# USB.net
KiCad netlist of a schematic drawn in Altium Designer
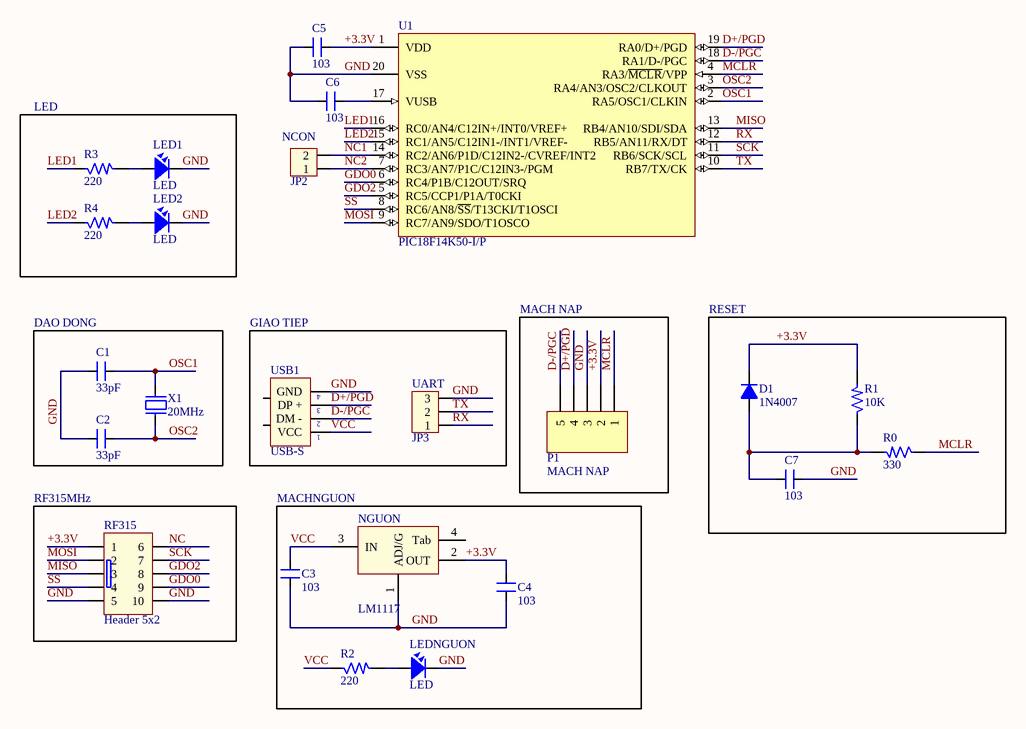
[diagram p0: USB.SchDoc]

(export (version "E")
  (design (tool "Eeschema 10.0.6"))
  (components
    (comp (ref "C1")
      (value "33pF")
      (footprint "SM-0805")
      (description "Cap SMD")
      (libsource (lib "syhaunguyen") (part "CM"))
    )
    (comp (ref "C2")
      (value "33pF")
      (footprint "SM-0805")
      (description "Cap SMD")
      (libsource (lib "syhaunguyen") (part "CM"))
    )
    (comp (ref "C3")
      (value "103")
      (footprint "SM-0805")
      (description "Cap SMD")
      (libsource (lib "syhaunguyen") (part "CM"))
    )
    (comp (ref "C4")
      (value "103")
      (footprint "SM-0805")
      (description "Cap SMD")
      (libsource (lib "syhaunguyen") (part "CM"))
    )
    (comp (ref "C5")
      (value "103")
      (footprint "SM-0805")
      (description "Cap SMD")
      (libsource (lib "syhaunguyen") (part "CM"))
    )
    (comp (ref "C6")
      (value "103")
      (footprint "CP1/2.5_SM")
      (description "Cap SMD")
      (libsource (lib "syhaunguyen") (part "CM"))
    )
    (comp (ref "C7")
      (value "103")
      (footprint "SM-0805")
      (description "Cap SMD")
      (libsource (lib "syhaunguyen") (part "CM"))
    )
    (comp (ref "D1")
      (value "1N4007")
      (footprint "D1A")
      (description "Diode 1A")
      (libsource (lib "syhaunguyen") (part "D1A"))
    )
    (comp (ref "LED1")
      (value "LED")
      (footprint "LED-3")
      (description "LED Single colour Green and Red")
      (libsource (lib "syhaunguyen") (part "LED"))
    )
    (comp (ref "LED2")
      (value "LED")
      (footprint "LED-3")
      (description "LED Single colour Green and Red")
      (libsource (lib "syhaunguyen") (part "LED"))
    )
    (comp (ref "LEDNGUON")
      (value "LED")
      (footprint "LED-3")
      (description "LED Single colour Green and Red")
      (libsource (lib "syhaunguyen") (part "LED"))
    )
    (comp (ref "NCON")
      (value "JP2")
      (footprint "CON2")
      (description "Connector 2")
      (libsource (lib "syhaunguyen") (part "Con2"))
    )
    (comp (ref "NGUON")
      (value "LM1117")
      (footprint "SOT223-4N")
      (description "3v3")
      (libsource (lib "syhaunguyen") (part "LM1117"))
    )
    (comp (ref "P1")
      (value "MACH NAP")
      (footprint "CON5")
      (description "Header, 5-Pin, Right Angle")
      (fields (field (name "PUBLISHER") "Altium Limited"))
      (libsource (lib "Miscellaneous Connectors") (part "Header 5H"))
    )
    (comp (ref "R0")
      (value "330")
      (footprint "SM-0805")
      (description "Resistor 1/4W")
      (libsource (lib "syhaunguyen") (part "R"))
    )
    (comp (ref "R1")
      (value "10K")
      (footprint "SM-0805")
      (description "Resistor 1/4W")
      (libsource (lib "syhaunguyen") (part "R"))
    )
    (comp (ref "R2")
      (value "220")
      (footprint "SM-0805")
      (description "Resistor 1/4W")
      (libsource (lib "syhaunguyen") (part "R"))
    )
    (comp (ref "R3")
      (value "220")
      (footprint "SM-0805")
      (description "Resistor 1/4W")
      (libsource (lib "syhaunguyen") (part "R"))
    )
    (comp (ref "R4")
      (value "220")
      (footprint "SM-0805")
      (description "Resistor 1/4W")
      (libsource (lib "syhaunguyen") (part "R"))
    )
    (comp (ref "RF315")
      (value "Header 5x2")
      (footprint "HED2X5_cen")
      (libsource (lib "syhaunguyen") (part "HED5x2"))
    )
    (comp (ref "U1")
      (value "PIC18F14K50-I/P")
      (footprint "SOP-20")
      (description "USB Flash Microcontroller with nanoWatt XLP Technology, 20-pin PDIP, Industrial Temperature")
      (fields (field (name "PUBLISHER") "Altium Limited"))
      (libsource (lib "Microchip Microcontroller 8-Bit PIC18") (part "PIC18F14K50-I/P"))
    )
    (comp (ref "UART")
      (value "JP3")
      (footprint "CON3")
      (description "Connector 3")
      (libsource (lib "syhaunguyen") (part "Con3"))
    )
    (comp (ref "USB1")
      (value "USB-S")
      (footprint "USB-A")
      (description "USB connector")
      (libsource (lib "syhaunguyen") (part "USB_S"))
    )
    (comp (ref "X1")
      (value "20MHz")
      (footprint "XT2")
      (description "Crystal For all Crystal 2pin.")
      (libsource (lib "syhaunguyen") (part "XT2"))
    )
  )
  (nets
    (net (code "1") (name "/+3.3V") (class "Default")
      (node (ref "C4") (pin "2") (pinfunction "2_2") (pintype "passive"))
      (node (ref "C5") (pin "2") (pinfunction "2_2") (pintype "passive"))
      (node (ref "D1") (pin "2") (pinfunction "K_2") (pintype "passive"))
      (node (ref "NGUON") (pin "2") (pinfunction "OUT_2") (pintype "passive"))
      (node (ref "P1") (pin "2") (pinfunction "2_2") (pintype "passive"))
      (node (ref "R1") (pin "2") (pinfunction "2_2") (pintype "passive"))
      (node (ref "RF315") (pin "1") (pinfunction "1_1") (pintype "passive"))
      (node (ref "U1") (pin "1") (pinfunction "VDD_1") (pintype "power_in"))
    )
    (net (code "2") (name "/D+{slash}PGD") (class "Default")
      (node (ref "P1") (pin "4") (pinfunction "4_4") (pintype "passive"))
      (node (ref "U1") (pin "19") (pinfunction "RA0/D+/PGD_19") (pintype "bidirectional"))
      (node (ref "USB1") (pin "3") (pinfunction "DP_+_3") (pintype "passive"))
    )
    (net (code "3") (name "/D-{slash}PGC") (class "Default")
      (node (ref "P1") (pin "5") (pinfunction "5_5") (pintype "passive"))
      (node (ref "U1") (pin "18") (pinfunction "RA1/D-/PGC_18") (pintype "bidirectional"))
      (node (ref "USB1") (pin "2") (pinfunction "DM_-_2") (pintype "passive"))
    )
    (net (code "4") (name "/GDO0") (class "Default")
      (node (ref "RF315") (pin "9") (pinfunction "9_9") (pintype "passive"))
      (node (ref "U1") (pin "6") (pinfunction "RC4/P1B/C12OUT/SRQ_6") (pintype "bidirectional"))
    )
    (net (code "5") (name "/GDO2") (class "Default")
      (node (ref "RF315") (pin "8") (pinfunction "8_8") (pintype "passive"))
      (node (ref "U1") (pin "5") (pinfunction "RC5/CCP1/P1A/T0CKI_5") (pintype "bidirectional"))
    )
    (net (code "6") (name "/GND") (class "Default")
      (node (ref "C1") (pin "1") (pinfunction "1_1") (pintype "passive"))
      (node (ref "C2") (pin "1") (pinfunction "1_1") (pintype "passive"))
      (node (ref "C3") (pin "1") (pinfunction "1_1") (pintype "passive"))
      (node (ref "C4") (pin "1") (pinfunction "1_1") (pintype "passive"))
      (node (ref "C5") (pin "1") (pinfunction "1_1") (pintype "passive"))
      (node (ref "C6") (pin "1") (pinfunction "1_1") (pintype "passive"))
      (node (ref "C7") (pin "1") (pinfunction "1_1") (pintype "passive"))
      (node (ref "LED1") (pin "2") (pinfunction "2_2") (pintype "passive"))
      (node (ref "LED2") (pin "2") (pinfunction "2_2") (pintype "passive"))
      (node (ref "LEDNGUON") (pin "2") (pinfunction "2_2") (pintype "passive"))
      (node (ref "NGUON") (pin "1") (pinfunction "ADJ/G_1") (pintype "passive"))
      (node (ref "P1") (pin "3") (pinfunction "3_3") (pintype "passive"))
      (node (ref "RF315") (pin "10") (pinfunction "10_10") (pintype "passive"))
      (node (ref "RF315") (pin "5") (pinfunction "5_5") (pintype "passive"))
      (node (ref "U1") (pin "20") (pinfunction "VSS_20") (pintype "power_in"))
      (node (ref "UART") (pin "3") (pinfunction "3_3") (pintype "passive"))
      (node (ref "USB1") (pin "4") (pinfunction "GND_4") (pintype "passive"))
    )
    (net (code "7") (name "/LED1") (class "Default")
      (node (ref "R3") (pin "1") (pinfunction "1_1") (pintype "passive"))
      (node (ref "U1") (pin "16") (pinfunction "RC0/AN4/C12IN+/INT0/VREF+_16") (pintype "bidirectional"))
    )
    (net (code "8") (name "/LED2") (class "Default")
      (node (ref "R4") (pin "1") (pinfunction "1_1") (pintype "passive"))
      (node (ref "U1") (pin "15") (pinfunction "RC1/AN5/C12IN1-/INT1/VREF-_15") (pintype "bidirectional"))
    )
    (net (code "9") (name "/MCLR") (class "Default")
      (node (ref "P1") (pin "1") (pinfunction "1_1") (pintype "passive"))
      (node (ref "R0") (pin "1") (pinfunction "1_1") (pintype "passive"))
      (node (ref "U1") (pin "4") (pinfunction "RA3/~{MCLR}/VPP_4") (pintype "input"))
    )
    (net (code "10") (name "/MISO") (class "Default")
      (node (ref "RF315") (pin "3") (pinfunction "3_3") (pintype "passive"))
      (node (ref "U1") (pin "13") (pinfunction "RB4/AN10/SDI/SDA_13") (pintype "bidirectional"))
    )
    (net (code "11") (name "/MOSI") (class "Default")
      (node (ref "RF315") (pin "2") (pinfunction "2_2") (pintype "passive"))
      (node (ref "U1") (pin "9") (pinfunction "RC7/AN9/SDO/T1OSCO_9") (pintype "bidirectional"))
    )
    (net (code "12") (name "/NC") (class "Default")
      (node (ref "RF315") (pin "6") (pinfunction "6_6") (pintype "passive"))
    )
    (net (code "13") (name "/NC1") (class "Default")
      (node (ref "NCON") (pin "2") (pinfunction "2_2") (pintype "passive"))
      (node (ref "U1") (pin "14") (pinfunction "RC2/AN6/P1D/C12IN2-/CVREF/INT2_14") (pintype "bidirectional"))
    )
    (net (code "14") (name "/NC2") (class "Default")
      (node (ref "NCON") (pin "1") (pinfunction "1_1") (pintype "passive"))
      (node (ref "U1") (pin "7") (pinfunction "RC3/AN7/P1C/C12IN3-/PGM_7") (pintype "bidirectional"))
    )
    (net (code "15") (name "/OSC1") (class "Default")
      (node (ref "C1") (pin "2") (pinfunction "2_2") (pintype "passive"))
      (node (ref "U1") (pin "2") (pinfunction "RA5/OSC1/CLKIN_2") (pintype "bidirectional"))
      (node (ref "X1") (pin "2") (pinfunction "2_2") (pintype "passive"))
    )
    (net (code "16") (name "/OSC2") (class "Default")
      (node (ref "C2") (pin "2") (pinfunction "2_2") (pintype "passive"))
      (node (ref "U1") (pin "3") (pinfunction "RA4/AN3/OSC2/CLKOUT_3") (pintype "bidirectional"))
      (node (ref "X1") (pin "1") (pinfunction "1_1") (pintype "passive"))
    )
    (net (code "17") (name "/RX") (class "Default")
      (node (ref "U1") (pin "12") (pinfunction "RB5/AN11/RX/DT_12") (pintype "bidirectional"))
      (node (ref "UART") (pin "1") (pinfunction "1_1") (pintype "passive"))
    )
    (net (code "18") (name "/SCK") (class "Default")
      (node (ref "RF315") (pin "7") (pinfunction "7_7") (pintype "passive"))
      (node (ref "U1") (pin "11") (pinfunction "RB6/SCK/SCL_11") (pintype "bidirectional"))
    )
    (net (code "19") (name "/SS") (class "Default")
      (node (ref "RF315") (pin "4") (pinfunction "4_4") (pintype "passive"))
      (node (ref "U1") (pin "8") (pinfunction "RC6/AN8/~{SS}/T13CKI/T1OSCI_8") (pintype "bidirectional"))
    )
    (net (code "20") (name "/TX") (class "Default")
      (node (ref "U1") (pin "10") (pinfunction "RB7/TX/CK_10") (pintype "bidirectional"))
      (node (ref "UART") (pin "2") (pinfunction "2_2") (pintype "passive"))
    )
    (net (code "21") (name "/VCC") (class "Default")
      (node (ref "C3") (pin "2") (pinfunction "2_2") (pintype "passive"))
      (node (ref "NGUON") (pin "3") (pinfunction "IN_3") (pintype "passive"))
      (node (ref "R2") (pin "1") (pinfunction "1_1") (pintype "passive"))
      (node (ref "USB1") (pin "1") (pinfunction "VCC_1") (pintype "passive"))
    )
    (net (code "22") (name "Net-(D1-A)") (class "Default")
      (node (ref "C7") (pin "2") (pinfunction "2_2") (pintype "passive"))
      (node (ref "D1") (pin "1") (pinfunction "A_1") (pintype "passive"))
      (node (ref "R0") (pin "2") (pinfunction "2_2") (pintype "passive"))
      (node (ref "R1") (pin "1") (pinfunction "1_1") (pintype "passive"))
    )
    (net (code "23") (name "Net-(LED1-Pad1)") (class "Default")
      (node (ref "LED1") (pin "1") (pinfunction "1_1") (pintype "passive"))
      (node (ref "R3") (pin "2") (pinfunction "2_2") (pintype "passive"))
    )
    (net (code "24") (name "Net-(LED2-Pad1)") (class "Default")
      (node (ref "LED2") (pin "1") (pinfunction "1_1") (pintype "passive"))
      (node (ref "R4") (pin "2") (pinfunction "2_2") (pintype "passive"))
    )
    (net (code "25") (name "Net-(LEDNGUON-Pad1)") (class "Default")
      (node (ref "LEDNGUON") (pin "1") (pinfunction "1_1") (pintype "passive"))
      (node (ref "R2") (pin "2") (pinfunction "2_2") (pintype "passive"))
    )
    (net (code "26") (name "Net-(U1-VUSB)") (class "Default")
      (node (ref "C6") (pin "2") (pinfunction "2_2") (pintype "passive"))
      (node (ref "U1") (pin "17") (pinfunction "VUSB_17") (pintype "input"))
    )
    (net (code "27") (name "unconnected-(NGUON-Tab-Pad4)") (class "Default")
      (node (ref "NGUON") (pin "4") (pinfunction "Tab_4") (pintype "passive"))
    )
    (net (code "28") (name "unconnected-(USB1-Pad5)") (class "Default")
      (node (ref "USB1") (pin "5") (pinfunction "5_5") (pintype "passive"))
    )
    (net (code "29") (name "unconnected-(USB1-Pad6)") (class "Default")
      (node (ref "USB1") (pin "6") (pinfunction "6_6") (pintype "passive"))
    )
  )
)
